# remote.net
KiCad netlist of a schematic drawn in EAGLE
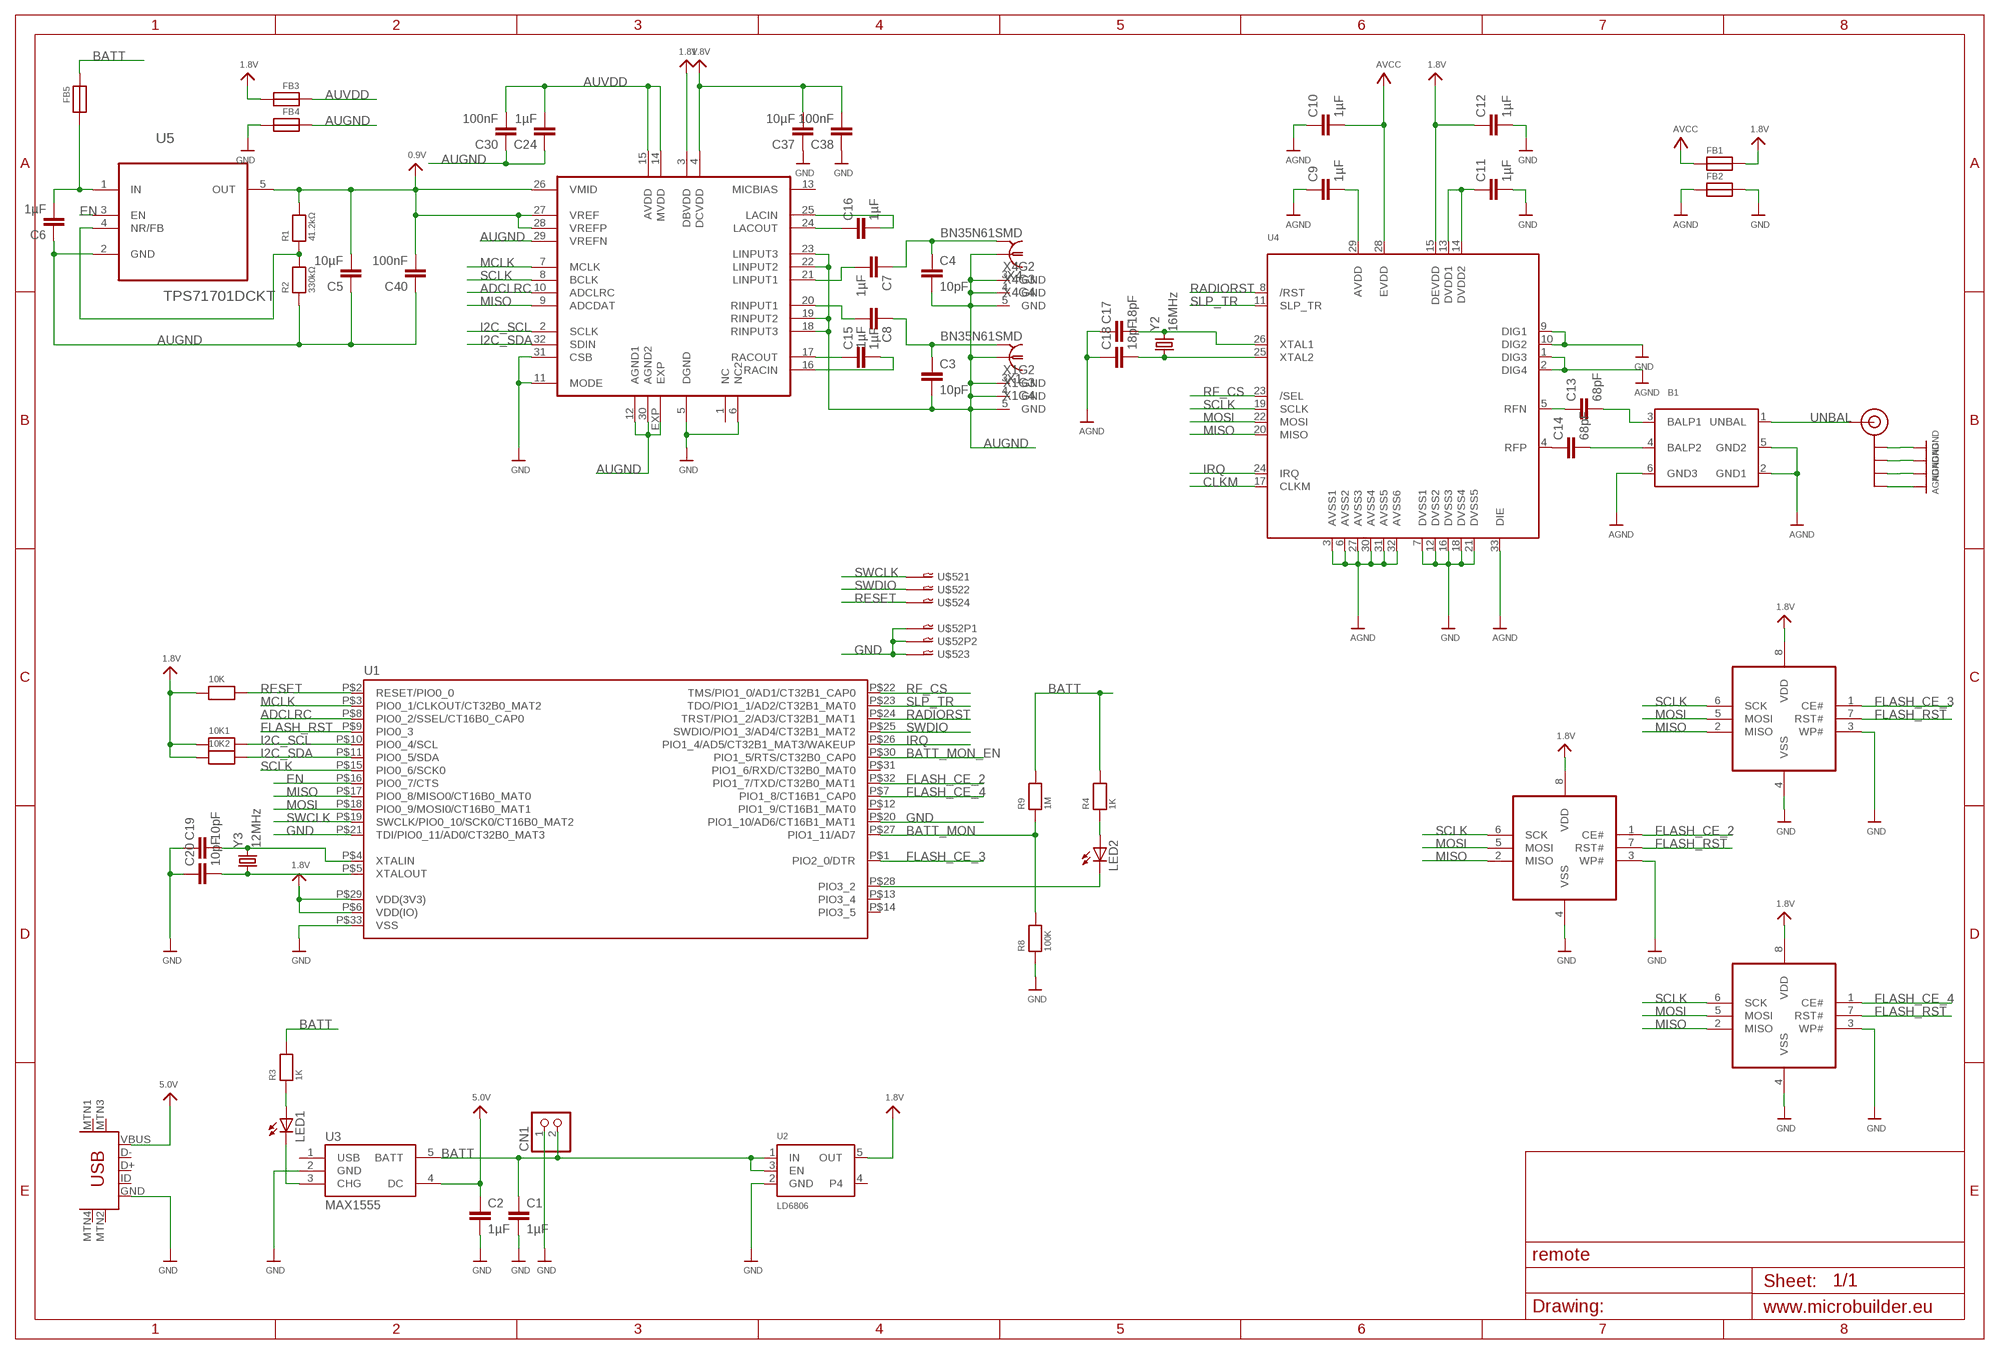
[diagram p0: schematic, sheet 1]

(export (version "E")
  (design (tool "Eeschema 10.0.6"))
  (components
    (comp (ref "10K")
      (value "RESISTOR0603MINI")
      (footprint "eagle-import:0603-MINI")
      (libsource (lib "eagle-import") (part "RESISTOR0603MINI"))
    )
    (comp (ref "10K1")
      (value "RESISTOR0603MINI")
      (footprint "eagle-import:0603-MINI")
      (libsource (lib "eagle-import") (part "RESISTOR0603MINI"))
    )
    (comp (ref "10K2")
      (value "RESISTOR0603MINI")
      (footprint "eagle-import:0603-MINI")
      (libsource (lib "eagle-import") (part "RESISTOR0603MINI"))
    )
    (comp (ref "B1")
      (value "BALUN+LP")
      (footprint "eagle-import:BALUN0805")
      (libsource (lib "eagle-import") (part "BALUN+LP"))
    )
    (comp (ref "C1")
      (value "1µF")
      (footprint "eagle-import:C0603K")
      (libsource (lib "eagle-import") (part "C-EUC0603K"))
    )
    (comp (ref "C2")
      (value "1µF")
      (footprint "eagle-import:C0603K")
      (libsource (lib "eagle-import") (part "C-EUC0603K"))
    )
    (comp (ref "C3")
      (value "10pF")
      (footprint "eagle-import:C0603K")
      (libsource (lib "eagle-import") (part "C-EUC0603K"))
    )
    (comp (ref "C4")
      (value "10pF")
      (footprint "eagle-import:C0603K")
      (libsource (lib "eagle-import") (part "C-EUC0603K"))
    )
    (comp (ref "C5")
      (value "10µF")
      (footprint "eagle-import:C0603K")
      (libsource (lib "eagle-import") (part "C-EUC0603K"))
    )
    (comp (ref "C6")
      (value "1µF")
      (footprint "eagle-import:C0603K")
      (libsource (lib "eagle-import") (part "C-EUC0603K"))
    )
    (comp (ref "C7")
      (value "1µF")
      (footprint "eagle-import:C0603K")
      (libsource (lib "eagle-import") (part "C-EUC0603K"))
    )
    (comp (ref "C8")
      (value "1µF")
      (footprint "eagle-import:C0603K")
      (libsource (lib "eagle-import") (part "C-EUC0603K"))
    )
    (comp (ref "C9")
      (value "1µF")
      (footprint "eagle-import:C0603K")
      (libsource (lib "eagle-import") (part "C-EUC0603K"))
    )
    (comp (ref "C10")
      (value "1µF")
      (footprint "eagle-import:C0603K")
      (libsource (lib "eagle-import") (part "C-EUC0603K"))
    )
    (comp (ref "C11")
      (value "1µF")
      (footprint "eagle-import:C0603K")
      (libsource (lib "eagle-import") (part "C-EUC0603K"))
    )
    (comp (ref "C12")
      (value "1µF")
      (footprint "eagle-import:C0603K")
      (libsource (lib "eagle-import") (part "C-EUC0603K"))
    )
    (comp (ref "C13")
      (value "68pF")
      (footprint "eagle-import:C0603K")
      (libsource (lib "eagle-import") (part "C-EUC0603K"))
    )
    (comp (ref "C14")
      (value "68pF")
      (footprint "eagle-import:C0603K")
      (libsource (lib "eagle-import") (part "C-EUC0603K"))
    )
    (comp (ref "C15")
      (value "1µF")
      (footprint "eagle-import:C0603K")
      (libsource (lib "eagle-import") (part "C-EUC0603K"))
    )
    (comp (ref "C16")
      (value "1µF")
      (footprint "eagle-import:C0603K")
      (libsource (lib "eagle-import") (part "C-EUC0603K"))
    )
    (comp (ref "C17")
      (value "18pF")
      (footprint "eagle-import:C0603K")
      (libsource (lib "eagle-import") (part "C-EUC0603K"))
    )
    (comp (ref "C18")
      (value "18pF")
      (footprint "eagle-import:C0603K")
      (libsource (lib "eagle-import") (part "C-EUC0603K"))
    )
    (comp (ref "C19")
      (value "10pF")
      (footprint "eagle-import:C0603K")
      (libsource (lib "eagle-import") (part "C-EUC0603K"))
    )
    (comp (ref "C20")
      (value "10pF")
      (footprint "eagle-import:C0603K")
      (libsource (lib "eagle-import") (part "C-EUC0603K"))
    )
    (comp (ref "C24")
      (value "1µF")
      (footprint "eagle-import:C0603K")
      (libsource (lib "eagle-import") (part "C-EUC0603K"))
    )
    (comp (ref "C30")
      (value "100nF")
      (footprint "eagle-import:C0603K")
      (libsource (lib "eagle-import") (part "C-EUC0603K"))
    )
    (comp (ref "C37")
      (value "10µF")
      (footprint "eagle-import:C0603K")
      (libsource (lib "eagle-import") (part "C-EUC0603K"))
    )
    (comp (ref "C38")
      (value "100nF")
      (footprint "eagle-import:C0603K")
      (libsource (lib "eagle-import") (part "C-EUC0603K"))
    )
    (comp (ref "C40")
      (value "100nF")
      (footprint "eagle-import:C0603K")
      (libsource (lib "eagle-import") (part "C-EUC0603K"))
    )
    (comp (ref "CN1")
      (value "JST_2PIN")
      (footprint "eagle-import:JSTPH2")
      (libsource (lib "eagle-import") (part "JST_2PIN"))
    )
    (comp (ref "FB1")
      (value "FERRITE")
      (footprint "eagle-import:0603")
      (libsource (lib "eagle-import") (part "FERRITE"))
    )
    (comp (ref "FB2")
      (value "FERRITE")
      (footprint "eagle-import:0603")
      (libsource (lib "eagle-import") (part "FERRITE"))
    )
    (comp (ref "FB3")
      (value "FERRITE")
      (footprint "eagle-import:0603")
      (libsource (lib "eagle-import") (part "FERRITE"))
    )
    (comp (ref "FB4")
      (value "FERRITE")
      (footprint "eagle-import:0603")
      (libsource (lib "eagle-import") (part "FERRITE"))
    )
    (comp (ref "FB5")
      (value "FERRITE")
      (footprint "eagle-import:0603")
      (libsource (lib "eagle-import") (part "FERRITE"))
    )
    (comp (ref "J$1")
      (value "SMA_EDGE")
      (footprint "eagle-import:SMA-EDGE")
      (libsource (lib "eagle-import") (part "SMA_EDGE"))
    )
    (comp (ref "LED1")
      (value "LEDCHIPLED_0603")
      (footprint "eagle-import:CHIPLED_0603")
      (libsource (lib "eagle-import") (part "LEDCHIPLED_0603"))
    )
    (comp (ref "LED2")
      (value "LEDCHIPLED_0603")
      (footprint "eagle-import:CHIPLED_0603")
      (libsource (lib "eagle-import") (part "LEDCHIPLED_0603"))
    )
    (comp (ref "R1")
      (value "41.2kΩ")
      (footprint "eagle-import:0603-MINI")
      (libsource (lib "eagle-import") (part "RESISTOR0603MINI"))
    )
    (comp (ref "R2")
      (value "330kΩ")
      (footprint "eagle-import:0603-MINI")
      (libsource (lib "eagle-import") (part "RESISTOR0603MINI"))
    )
    (comp (ref "R3")
      (value "1K")
      (footprint "eagle-import:0603-MINI")
      (libsource (lib "eagle-import") (part "RESISTOR0603MINI"))
    )
    (comp (ref "R4")
      (value "1K")
      (footprint "eagle-import:0603-MINI")
      (libsource (lib "eagle-import") (part "RESISTOR0603MINI"))
    )
    (comp (ref "R8")
      (value "100K")
      (footprint "eagle-import:0603-MINI")
      (libsource (lib "eagle-import") (part "RESISTOR0603MINI"))
    )
    (comp (ref "R9")
      (value "1M")
      (footprint "eagle-import:0603-MINI")
      (libsource (lib "eagle-import") (part "RESISTOR0603MINI"))
    )
    (comp (ref "U$1")
      (value "SST25WF")
      (footprint "eagle-import:ZA")
      (libsource (lib "eagle-import") (part "SST25WF"))
    )
    (comp (ref "U$14")
      (value "WM8737")
      (footprint "eagle-import:DM030FL")
      (libsource (lib "eagle-import") (part "WM8737"))
    )
    (comp (ref "U$16")
      (value "USB-MINIB-5PIN")
      (footprint "eagle-import:USB-MINIB")
      (libsource (lib "eagle-import") (part "USB-MINIB-5PIN"))
    )
    (comp (ref "U$22")
      (value "SST25WF")
      (footprint "eagle-import:ZA")
      (libsource (lib "eagle-import") (part "SST25WF"))
    )
    (comp (ref "U$26")
      (value "SST25WF")
      (footprint "eagle-import:ZA")
      (libsource (lib "eagle-import") (part "SST25WF"))
    )
    (comp (ref "U$52")
      (value "SM04B-SURS-TF")
      (footprint "eagle-import:SM04B-SURS-TF")
      (libsource (lib "eagle-import") (part "SM04B-SURS-TF"))
    )
    (comp (ref "U1")
      (value "LPC1113/4_QFN")
      (footprint "eagle-import:HVQFN33-7X7")
      (fields (field (name "MANF") "NXP"))
      (libsource (lib "eagle-import") (part "LPC1113/4_QFN"))
    )
    (comp (ref "U2")
      (value "LD6806")
      (footprint "eagle-import:SOT23-5")
      (libsource (lib "eagle-import") (part "VREG_SOT23-5"))
    )
    (comp (ref "U3")
      (value "MAX1555")
      (footprint "eagle-import:SOT23-5")
      (libsource (lib "eagle-import") (part "MAX1555"))
    )
    (comp (ref "U4")
      (value "AT86RF212")
      (footprint "eagle-import:32QN2")
      (libsource (lib "eagle-import") (part "AT86RF212"))
    )
    (comp (ref "U5")
      (value "TPS71701DCKT")
      (footprint "eagle-import:SOT65P210X110-5N")
      (libsource (lib "eagle-import") (part "TPS71701DCKT"))
    )
    (comp (ref "X1")
      (value "BN35N61SMD")
      (footprint "eagle-import:B35N61_SMD")
      (libsource (lib "eagle-import") (part "BN35N61SMD"))
    )
    (comp (ref "X4")
      (value "BN35N61SMD")
      (footprint "eagle-import:B35N61_SMD")
      (libsource (lib "eagle-import") (part "BN35N61SMD"))
    )
    (comp (ref "Y2")
      (value "16MHz")
      (footprint "eagle-import:CRYSTAL-SMD-5X3")
      (libsource (lib "eagle-import") (part "CRYSTAL5X3"))
    )
    (comp (ref "Y3")
      (value "12MHz")
      (footprint "eagle-import:CRYSTAL-SMD-5X3")
      (libsource (lib "eagle-import") (part "CRYSTAL5X3"))
    )
  )
  (nets
    (net (code "1") (name "/ADCLRC") (class "Default")
      (node (ref "U$14") (pin "10") (pinfunction "ADCLRC_10") (pintype "bidirectional"))
      (node (ref "U1") (pin "P$8") (pinfunction "PIO0_2/SSEL/CT16B0_CAP0_P$8") (pintype "bidirectional"))
    )
    (net (code "2") (name "/AUGND") (class "Default")
      (node (ref "C24") (pin "1") (pinfunction "1_1") (pintype "passive"))
      (node (ref "C3") (pin "2") (pinfunction "2_2") (pintype "passive"))
      (node (ref "C30") (pin "1") (pinfunction "1_1") (pintype "passive"))
      (node (ref "C4") (pin "2") (pinfunction "2_2") (pintype "passive"))
      (node (ref "C40") (pin "1") (pinfunction "1_1") (pintype "passive"))
      (node (ref "C5") (pin "1") (pinfunction "1_1") (pintype "passive"))
      (node (ref "C6") (pin "1") (pinfunction "1_1") (pintype "passive"))
      (node (ref "FB4") (pin "1") (pinfunction "P$1_1") (pintype "bidirectional"))
      (node (ref "R2") (pin "1") (pinfunction "1_1") (pintype "passive"))
      (node (ref "U$14") (pin "12") (pinfunction "AGND1_12") (pintype "bidirectional"))
      (node (ref "U$14") (pin "18") (pinfunction "RINPUT3_18") (pintype "bidirectional"))
      (node (ref "U$14") (pin "19") (pinfunction "RINPUT2_19") (pintype "bidirectional"))
      (node (ref "U$14") (pin "22") (pinfunction "LINPUT2_22") (pintype "bidirectional"))
      (node (ref "U$14") (pin "23") (pinfunction "LINPUT3_23") (pintype "bidirectional"))
      (node (ref "U$14") (pin "29") (pinfunction "VREFN_29") (pintype "bidirectional"))
      (node (ref "U$14") (pin "30") (pinfunction "AGND2_30") (pintype "bidirectional"))
      (node (ref "U$14") (pin "EXP") (pinfunction "EXP_EXP") (pintype "bidirectional"))
      (node (ref "U5") (pin "2") (pinfunction "GND_2") (pintype "passive"))
      (node (ref "X1") (pin "2") (pinfunction "1_2") (pintype "passive"))
      (node (ref "X1") (pin "3") (pinfunction "GND_3") (pintype "power_in"))
      (node (ref "X1") (pin "4") (pinfunction "GND_4") (pintype "power_in"))
      (node (ref "X1") (pin "5") (pinfunction "GND_5") (pintype "power_in"))
      (node (ref "X4") (pin "2") (pinfunction "1_2") (pintype "passive"))
      (node (ref "X4") (pin "3") (pinfunction "GND_3") (pintype "power_in"))
      (node (ref "X4") (pin "4") (pinfunction "GND_4") (pintype "power_in"))
      (node (ref "X4") (pin "5") (pinfunction "GND_5") (pintype "power_in"))
    )
    (net (code "3") (name "/AUVDD") (class "Default")
      (node (ref "C24") (pin "2") (pinfunction "2_2") (pintype "passive"))
      (node (ref "C30") (pin "2") (pinfunction "2_2") (pintype "passive"))
      (node (ref "FB3") (pin "1") (pinfunction "P$1_1") (pintype "bidirectional"))
      (node (ref "U$14") (pin "14") (pinfunction "MVDD_14") (pintype "bidirectional"))
      (node (ref "U$14") (pin "15") (pinfunction "AVDD_15") (pintype "bidirectional"))
    )
    (net (code "4") (name "/BATT") (class "Default")
      (node (ref "C1") (pin "1") (pinfunction "1_1") (pintype "passive"))
      (node (ref "CN1") (pin "2") (pinfunction "2_2") (pintype "passive"))
      (node (ref "FB5") (pin "1") (pinfunction "P$1_1") (pintype "bidirectional"))
      (node (ref "R3") (pin "2") (pinfunction "2_2") (pintype "passive"))
      (node (ref "R4") (pin "2") (pinfunction "2_2") (pintype "passive"))
      (node (ref "R9") (pin "2") (pinfunction "2_2") (pintype "passive"))
      (node (ref "U2") (pin "1") (pinfunction "IN_1") (pintype "bidirectional"))
      (node (ref "U2") (pin "3") (pinfunction "EN_3") (pintype "bidirectional"))
      (node (ref "U3") (pin "5") (pinfunction "BATT_5") (pintype "bidirectional"))
    )
    (net (code "5") (name "/BATT_MON") (class "Default")
      (node (ref "R8") (pin "2") (pinfunction "2_2") (pintype "passive"))
      (node (ref "R9") (pin "1") (pinfunction "1_1") (pintype "passive"))
      (node (ref "U1") (pin "P$27") (pinfunction "PIO1_11/AD7_P$27") (pintype "bidirectional"))
    )
    (net (code "6") (name "/BATT_MON_EN") (class "Default")
      (node (ref "U1") (pin "P$30") (pinfunction "PIO1_5/RTS/CT32B0_CAP0_P$30") (pintype "bidirectional"))
    )
    (net (code "7") (name "/CLKM") (class "Default")
      (node (ref "U4") (pin "17") (pinfunction "CLKM_17") (pintype "bidirectional"))
    )
    (net (code "8") (name "/EN") (class "Default")
      (node (ref "U1") (pin "P$16") (pinfunction "PIO0_7/CTS_P$16") (pintype "bidirectional"))
      (node (ref "U5") (pin "3") (pinfunction "EN_3") (pintype "input"))
    )
    (net (code "9") (name "/FLASH_CE_2") (class "Default")
      (node (ref "U$26") (pin "1") (pinfunction "CE#_1") (pintype "bidirectional"))
      (node (ref "U1") (pin "P$32") (pinfunction "PIO1_7/TXD/CT32B0_MAT1_P$32") (pintype "bidirectional"))
    )
    (net (code "10") (name "/FLASH_CE_3") (class "Default")
      (node (ref "U$22") (pin "1") (pinfunction "CE#_1") (pintype "bidirectional"))
      (node (ref "U1") (pin "P$1") (pinfunction "PIO2_0/DTR_P$1") (pintype "bidirectional"))
    )
    (net (code "11") (name "/FLASH_CE_4") (class "Default")
      (node (ref "U$1") (pin "1") (pinfunction "CE#_1") (pintype "bidirectional"))
      (node (ref "U1") (pin "P$7") (pinfunction "PIO1_8/CT16B1_CAP0_P$7") (pintype "bidirectional"))
    )
    (net (code "12") (name "/FLASH_RST") (class "Default")
      (node (ref "U$1") (pin "7") (pinfunction "RST#_7") (pintype "bidirectional"))
      (node (ref "U$22") (pin "7") (pinfunction "RST#_7") (pintype "bidirectional"))
      (node (ref "U$26") (pin "7") (pinfunction "RST#_7") (pintype "bidirectional"))
      (node (ref "U1") (pin "P$9") (pinfunction "PIO0_3_P$9") (pintype "bidirectional"))
    )
    (net (code "13") (name "/I2C_SCL") (class "Default")
      (node (ref "10K1") (pin "2") (pinfunction "2_2") (pintype "passive"))
      (node (ref "U$14") (pin "2") (pinfunction "SCLK_2") (pintype "bidirectional"))
      (node (ref "U1") (pin "P$10") (pinfunction "PIO0_4/SCL_P$10") (pintype "bidirectional"))
    )
    (net (code "14") (name "/I2C_SDA") (class "Default")
      (node (ref "10K2") (pin "2") (pinfunction "2_2") (pintype "passive"))
      (node (ref "U$14") (pin "32") (pinfunction "SDIN_32") (pintype "bidirectional"))
      (node (ref "U1") (pin "P$11") (pinfunction "PIO0_5/SDA_P$11") (pintype "bidirectional"))
    )
    (net (code "15") (name "/IRQ") (class "Default")
      (node (ref "U1") (pin "P$26") (pinfunction "PIO1_4/AD5/CT32B1_MAT3/WAKEUP_P$26") (pintype "bidirectional"))
      (node (ref "U4") (pin "24") (pinfunction "IRQ_24") (pintype "bidirectional"))
    )
    (net (code "16") (name "/MCLK") (class "Default")
      (node (ref "U$14") (pin "7") (pinfunction "MCLK_7") (pintype "bidirectional"))
      (node (ref "U1") (pin "P$3") (pinfunction "PIO0_1/CLKOUT/CT32B0_MAT2_P$3") (pintype "bidirectional"))
    )
    (net (code "17") (name "/MISO") (class "Default")
      (node (ref "U$1") (pin "2") (pinfunction "MISO_2") (pintype "bidirectional"))
      (node (ref "U$14") (pin "9") (pinfunction "ADCDAT_9") (pintype "bidirectional"))
      (node (ref "U$22") (pin "2") (pinfunction "MISO_2") (pintype "bidirectional"))
      (node (ref "U$26") (pin "2") (pinfunction "MISO_2") (pintype "bidirectional"))
      (node (ref "U1") (pin "P$17") (pinfunction "PIO0_8/MISO0/CT16B0_MAT0_P$17") (pintype "bidirectional"))
      (node (ref "U4") (pin "20") (pinfunction "MISO_20") (pintype "bidirectional"))
    )
    (net (code "18") (name "/MOSI") (class "Default")
      (node (ref "U$1") (pin "5") (pinfunction "MOSI_5") (pintype "bidirectional"))
      (node (ref "U$22") (pin "5") (pinfunction "MOSI_5") (pintype "bidirectional"))
      (node (ref "U$26") (pin "5") (pinfunction "MOSI_5") (pintype "bidirectional"))
      (node (ref "U1") (pin "P$18") (pinfunction "PIO0_9/MOSI0/CT16B0_MAT1_P$18") (pintype "bidirectional"))
      (node (ref "U4") (pin "22") (pinfunction "MOSI_22") (pintype "bidirectional"))
    )
    (net (code "19") (name "/RADIORST") (class "Default")
      (node (ref "U1") (pin "P$24") (pinfunction "TRST/PIO1_2/AD3/CT32B1_MAT1_P$24") (pintype "bidirectional"))
      (node (ref "U4") (pin "8") (pinfunction "/RST_8") (pintype "bidirectional"))
    )
    (net (code "20") (name "/RESET") (class "Default")
      (node (ref "10K") (pin "2") (pinfunction "2_2") (pintype "passive"))
      (node (ref "U$52") (pin "4") (pinfunction "1_4") (pintype "passive"))
      (node (ref "U1") (pin "P$2") (pinfunction "RESET/PIO0_0_P$2") (pintype "bidirectional"))
    )
    (net (code "21") (name "/RF_CS") (class "Default")
      (node (ref "U1") (pin "P$22") (pinfunction "TMS/PIO1_0/AD1/CT32B1_CAP0_P$22") (pintype "bidirectional"))
      (node (ref "U4") (pin "23") (pinfunction "/SEL_23") (pintype "bidirectional"))
    )
    (net (code "22") (name "/SCLK") (class "Default")
      (node (ref "U$1") (pin "6") (pinfunction "SCK_6") (pintype "bidirectional"))
      (node (ref "U$14") (pin "8") (pinfunction "BCLK_8") (pintype "bidirectional"))
      (node (ref "U$22") (pin "6") (pinfunction "SCK_6") (pintype "bidirectional"))
      (node (ref "U$26") (pin "6") (pinfunction "SCK_6") (pintype "bidirectional"))
      (node (ref "U1") (pin "P$15") (pinfunction "PIO0_6/SCK0_P$15") (pintype "bidirectional"))
      (node (ref "U4") (pin "19") (pinfunction "SCLK_19") (pintype "bidirectional"))
    )
    (net (code "23") (name "/SLP_TR") (class "Default")
      (node (ref "U1") (pin "P$23") (pinfunction "TDO/PIO1_1/AD2/CT32B1_MAT0_P$23") (pintype "bidirectional"))
      (node (ref "U4") (pin "11") (pinfunction "SLP_TR_11") (pintype "bidirectional"))
    )
    (net (code "24") (name "/SWCLK") (class "Default")
      (node (ref "U$52") (pin "1") (pinfunction "1_1") (pintype "passive"))
      (node (ref "U1") (pin "P$19") (pinfunction "SWCLK/PIO0_10/SCK0/CT16B0_MAT2_P$19") (pintype "bidirectional"))
    )
    (net (code "25") (name "/SWDIO") (class "Default")
      (node (ref "U$52") (pin "2") (pinfunction "1_2") (pintype "passive"))
      (node (ref "U1") (pin "P$25") (pinfunction "SWDIO/PIO1_3/AD4/CT32B1_MAT2_P$25") (pintype "bidirectional"))
    )
    (net (code "26") (name "/UNBAL") (class "Default")
      (node (ref "B1") (pin "1") (pinfunction "UNBAL_1") (pintype "bidirectional"))
      (node (ref "J$1") (pin "SIG") (pinfunction "SIGNAL_SIG") (pintype "bidirectional"))
    )
    (net (code "27") (name "0.9V") (class "Default")
      (node (ref "C40") (pin "2") (pinfunction "2_2") (pintype "passive"))
      (node (ref "C5") (pin "2") (pinfunction "2_2") (pintype "passive"))
      (node (ref "R1") (pin "2") (pinfunction "2_2") (pintype "passive"))
      (node (ref "U$14") (pin "26") (pinfunction "VMID_26") (pintype "bidirectional"))
      (node (ref "U$14") (pin "27") (pinfunction "VREF_27") (pintype "bidirectional"))
      (node (ref "U$14") (pin "28") (pinfunction "VREFP_28") (pintype "bidirectional"))
      (node (ref "U5") (pin "5") (pinfunction "OUT_5") (pintype "output"))
    )
    (net (code "28") (name "1.8V") (class "Default")
      (node (ref "10K") (pin "1") (pinfunction "1_1") (pintype "passive"))
      (node (ref "10K1") (pin "1") (pinfunction "1_1") (pintype "passive"))
      (node (ref "10K2") (pin "1") (pinfunction "1_1") (pintype "passive"))
      (node (ref "C12") (pin "1") (pinfunction "1_1") (pintype "passive"))
      (node (ref "C37") (pin "2") (pinfunction "2_2") (pintype "passive"))
      (node (ref "C38") (pin "2") (pinfunction "2_2") (pintype "passive"))
      (node (ref "FB1") (pin "2") (pinfunction "P$2_2") (pintype "bidirectional"))
      (node (ref "FB3") (pin "2") (pinfunction "P$2_2") (pintype "bidirectional"))
      (node (ref "U$1") (pin "8") (pinfunction "VDD_8") (pintype "bidirectional"))
      (node (ref "U$14") (pin "3") (pinfunction "DBVDD_3") (pintype "bidirectional"))
      (node (ref "U$14") (pin "4") (pinfunction "DCVDD_4") (pintype "bidirectional"))
      (node (ref "U$22") (pin "8") (pinfunction "VDD_8") (pintype "bidirectional"))
      (node (ref "U$26") (pin "8") (pinfunction "VDD_8") (pintype "bidirectional"))
      (node (ref "U1") (pin "P$29") (pinfunction "VDD(3V3)_P$29") (pintype "power_in"))
      (node (ref "U1") (pin "P$6") (pinfunction "VDD(IO)_P$6") (pintype "power_in"))
      (node (ref "U2") (pin "5") (pinfunction "OUT_5") (pintype "bidirectional"))
      (node (ref "U4") (pin "15") (pinfunction "DEVDD_15") (pintype "bidirectional"))
    )
    (net (code "29") (name "5.0V") (class "Default")
      (node (ref "C2") (pin "1") (pinfunction "1_1") (pintype "passive"))
      (node (ref "U$16") (pin "VBUS") (pinfunction "VBUS_VBUS") (pintype "bidirectional"))
      (node (ref "U3") (pin "4") (pinfunction "DC_4") (pintype "bidirectional"))
    )
    (net (code "30") (name "AGND") (class "Default")
      (node (ref "B1") (pin "2") (pinfunction "GND1_2") (pintype "bidirectional"))
      (node (ref "B1") (pin "5") (pinfunction "GND2_5") (pintype "bidirectional"))
      (node (ref "B1") (pin "6") (pinfunction "GND3_6") (pintype "bidirectional"))
      (node (ref "C10") (pin "1") (pinfunction "1_1") (pintype "passive"))
      (node (ref "C17") (pin "1") (pinfunction "1_1") (pintype "passive"))
      (node (ref "C18") (pin "1") (pinfunction "1_1") (pintype "passive"))
      (node (ref "C9") (pin "1") (pinfunction "1_1") (pintype "passive"))
      (node (ref "FB2") (pin "1") (pinfunction "P$1_1") (pintype "bidirectional"))
      (node (ref "J$1") (pin "GND@0") (pinfunction "GND_GND@0") (pintype "bidirectional"))
      (node (ref "J$1") (pin "GND@1") (pinfunction "GND_GND@1") (pintype "bidirectional"))
      (node (ref "J$1") (pin "GND@2") (pinfunction "GND_GND@2") (pintype "bidirectional"))
      (node (ref "J$1") (pin "GND@3") (pinfunction "GND_GND@3") (pintype "bidirectional"))
      (node (ref "U4") (pin "1") (pinfunction "DIG3_1") (pintype "bidirectional"))
      (node (ref "U4") (pin "2") (pinfunction "DIG4_2") (pintype "bidirectional"))
      (node (ref "U4") (pin "27") (pinfunction "AVSS3_27") (pintype "bidirectional"))
      (node (ref "U4") (pin "3") (pinfunction "AVSS1_3") (pintype "bidirectional"))
      (node (ref "U4") (pin "30") (pinfunction "AVSS4_30") (pintype "bidirectional"))
      (node (ref "U4") (pin "31") (pinfunction "AVSS5_31") (pintype "bidirectional"))
      (node (ref "U4") (pin "32") (pinfunction "AVSS6_32") (pintype "bidirectional"))
      (node (ref "U4") (pin "33") (pinfunction "DIE_33") (pintype "bidirectional"))
      (node (ref "U4") (pin "6") (pinfunction "AVSS2_6") (pintype "bidirectional"))
    )
    (net (code "31") (name "AVCC") (class "Default")
      (node (ref "C10") (pin "2") (pinfunction "2_2") (pintype "passive"))
      (node (ref "FB1") (pin "1") (pinfunction "P$1_1") (pintype "bidirectional"))
      (node (ref "U4") (pin "28") (pinfunction "EVDD_28") (pintype "bidirectional"))
    )
    (net (code "32") (name "GND") (class "Default")
      (node (ref "C1") (pin "2") (pinfunction "2_2") (pintype "passive"))
      (node (ref "C11") (pin "2") (pinfunction "2_2") (pintype "passive"))
      (node (ref "C12") (pin "2") (pinfunction "2_2") (pintype "passive"))
      (node (ref "C19") (pin "1") (pinfunction "1_1") (pintype "passive"))
      (node (ref "C2") (pin "2") (pinfunction "2_2") (pintype "passive"))
      (node (ref "C20") (pin "1") (pinfunction "1_1") (pintype "passive"))
      (node (ref "C37") (pin "1") (pinfunction "1_1") (pintype "passive"))
      (node (ref "C38") (pin "1") (pinfunction "1_1") (pintype "passive"))
      (node (ref "CN1") (pin "1") (pinfunction "1_1") (pintype "passive"))
      (node (ref "FB2") (pin "2") (pinfunction "P$2_2") (pintype "bidirectional"))
      (node (ref "FB4") (pin "2") (pinfunction "P$2_2") (pintype "bidirectional"))
      (node (ref "R8") (pin "1") (pinfunction "1_1") (pintype "passive"))
      (node (ref "U$1") (pin "3") (pinfunction "WP#_3") (pintype "bidirectional"))
      (node (ref "U$1") (pin "4") (pinfunction "VSS_4") (pintype "bidirectional"))
      (node (ref "U$14") (pin "11") (pinfunction "MODE_11") (pintype "bidirectional"))
      (node (ref "U$14") (pin "31") (pinfunction "CSB_31") (pintype "bidirectional"))
      (node (ref "U$14") (pin "5") (pinfunction "DGND_5") (pintype "bidirectional"))
      (node (ref "U$14") (pin "6") (pinfunction "NC2_6") (pintype "bidirectional"))
      (node (ref "U$16") (pin "GND") (pinfunction "GND_GND") (pintype "bidirectional"))
      (node (ref "U$22") (pin "3") (pinfunction "WP#_3") (pintype "bidirectional"))
      (node (ref "U$22") (pin "4") (pinfunction "VSS_4") (pintype "bidirectional"))
      (node (ref "U$26") (pin "3") (pinfunction "WP#_3") (pintype "bidirectional"))
      (node (ref "U$26") (pin "4") (pinfunction "VSS_4") (pintype "bidirectional"))
      (node (ref "U$52") (pin "3") (pinfunction "1_3") (pintype "passive"))
      (node (ref "U$52") (pin "GND1") (pinfunction "1_GND1") (pintype "passive"))
      (node (ref "U$52") (pin "GND2") (pinfunction "1_GND2") (pintype "passive"))
      (node (ref "U1") (pin "P$20") (pinfunction "PIO1_10/AD6/CT16B1_MAT1_P$20") (pintype "bidirectional"))
      (node (ref "U1") (pin "P$21") (pinfunction "TDI/PIO0_11/AD0/CT32B0_MAT3_P$21") (pintype "bidirectional"))
      (node (ref "U1") (pin "P$33") (pinfunction "VSS_P$33") (pintype "power_in"))
      (node (ref "U2") (pin "2") (pinfunction "GND_2") (pintype "bidirectional"))
      (node (ref "U3") (pin "2") (pinfunction "GND_2") (pintype "bidirectional"))
      (node (ref "U4") (pin "10") (pinfunction "DIG2_10") (pintype "bidirectional"))
      (node (ref "U4") (pin "12") (pinfunction "DVSS2_12") (pintype "bidirectional"))
      (node (ref "U4") (pin "16") (pinfunction "DVSS3_16") (pintype "bidirectional"))
      (node (ref "U4") (pin "18") (pinfunction "DVSS4_18") (pintype "bidirectional"))
      (node (ref "U4") (pin "21") (pinfunction "DVSS5_21") (pintype "bidirectional"))
      (node (ref "U4") (pin "7") (pinfunction "DVSS1_7") (pintype "bidirectional"))
      (node (ref "U4") (pin "9") (pinfunction "DIG1_9") (pintype "bidirectional"))
    )
    (net (code "33") (name "Net-(B1-BALP1)") (class "Default")
      (node (ref "B1") (pin "3") (pinfunction "BALP1_3") (pintype "bidirectional"))
      (node (ref "C13") (pin "2") (pinfunction "2_2") (pintype "passive"))
    )
    (net (code "34") (name "Net-(B1-BALP2)") (class "Default")
      (node (ref "B1") (pin "4") (pinfunction "BALP2_4") (pintype "bidirectional"))
      (node (ref "C14") (pin "2") (pinfunction "2_2") (pintype "passive"))
    )
    (net (code "35") (name "Net-(FB5-P$2)") (class "Default")
      (node (ref "C6") (pin "2") (pinfunction "2_2") (pintype "passive"))
      (node (ref "FB5") (pin "2") (pinfunction "P$2_2") (pintype "bidirectional"))
      (node (ref "U5") (pin "1") (pinfunction "IN_1") (pintype "power_in"))
    )
    (net (code "36") (name "Net-(LED1-PadA)") (class "Default")
      (node (ref "LED1") (pin "A") (pinfunction "A_A") (pintype "passive"))
      (node (ref "R3") (pin "1") (pinfunction "1_1") (pintype "passive"))
    )
    (net (code "37") (name "Net-(LED2-PadA)") (class "Default")
      (node (ref "LED2") (pin "A") (pinfunction "A_A") (pintype "passive"))
      (node (ref "R4") (pin "1") (pinfunction "1_1") (pintype "passive"))
    )
    (net (code "38") (name "Net-(U$14-LACIN)") (class "Default")
      (node (ref "C16") (pin "2") (pinfunction "2_2") (pintype "passive"))
      (node (ref "U$14") (pin "25") (pinfunction "LACIN_25") (pintype "bidirectional"))
    )
    (net (code "39") (name "Net-(U$14-LACOUT)") (class "Default")
      (node (ref "C16") (pin "1") (pinfunction "1_1") (pintype "passive"))
      (node (ref "U$14") (pin "24") (pinfunction "LACOUT_24") (pintype "bidirectional"))
    )
    (net (code "40") (name "Net-(U$14-LINPUT1)") (class "Default")
      (node (ref "C7") (pin "2") (pinfunction "2_2") (pintype "passive"))
      (node (ref "U$14") (pin "21") (pinfunction "LINPUT1_21") (pintype "bidirectional"))
    )
    (net (code "41") (name "Net-(U$14-RACIN)") (class "Default")
      (node (ref "C15") (pin "2") (pinfunction "2_2") (pintype "passive"))
      (node (ref "U$14") (pin "16") (pinfunction "RACIN_16") (pintype "bidirectional"))
    )
    (net (code "42") (name "Net-(U$14-RACOUT)") (class "Default")
      (node (ref "C15") (pin "1") (pinfunction "1_1") (pintype "passive"))
      (node (ref "U$14") (pin "17") (pinfunction "RACOUT_17") (pintype "bidirectional"))
    )
    (net (code "43") (name "Net-(U$14-RINPUT1)") (class "Default")
      (node (ref "C8") (pin "2") (pinfunction "2_2") (pintype "passive"))
      (node (ref "U$14") (pin "20") (pinfunction "RINPUT1_20") (pintype "bidirectional"))
    )
    (net (code "44") (name "Net-(U1-PIO3_2)") (class "Default")
      (node (ref "LED2") (pin "C") (pinfunction "C_C") (pintype "passive"))
      (node (ref "U1") (pin "P$28") (pinfunction "PIO3_2_P$28") (pintype "bidirectional"))
    )
    (net (code "45") (name "Net-(U1-XTALIN)") (class "Default")
      (node (ref "C19") (pin "2") (pinfunction "2_2") (pintype "passive"))
      (node (ref "U1") (pin "P$4") (pinfunction "XTALIN_P$4") (pintype "input"))
      (node (ref "Y3") (pin "3") (pinfunction "2_3") (pintype "passive"))
    )
    (net (code "46") (name "Net-(U1-XTALOUT)") (class "Default")
      (node (ref "C20") (pin "2") (pinfunction "2_2") (pintype "passive"))
      (node (ref "U1") (pin "P$5") (pinfunction "XTALOUT_P$5") (pintype "output"))
      (node (ref "Y3") (pin "1") (pinfunction "1_1") (pintype "passive"))
    )
    (net (code "47") (name "Net-(U3-CHG)") (class "Default")
      (node (ref "LED1") (pin "C") (pinfunction "C_C") (pintype "passive"))
      (node (ref "U3") (pin "3") (pinfunction "CHG_3") (pintype "bidirectional"))
    )
    (net (code "48") (name "Net-(U4-AVDD)") (class "Default")
      (node (ref "C9") (pin "2") (pinfunction "2_2") (pintype "passive"))
      (node (ref "U4") (pin "29") (pinfunction "AVDD_29") (pintype "bidirectional"))
    )
    (net (code "49") (name "Net-(U4-DVDD1)") (class "Default")
      (node (ref "C11") (pin "1") (pinfunction "1_1") (pintype "passive"))
      (node (ref "U4") (pin "13") (pinfunction "DVDD1_13") (pintype "bidirectional"))
      (node (ref "U4") (pin "14") (pinfunction "DVDD2_14") (pintype "bidirectional"))
    )
    (net (code "50") (name "Net-(U4-RFN)") (class "Default")
      (node (ref "C13") (pin "1") (pinfunction "1_1") (pintype "passive"))
      (node (ref "U4") (pin "5") (pinfunction "RFN_5") (pintype "bidirectional"))
    )
    (net (code "51") (name "Net-(U4-RFP)") (class "Default")
      (node (ref "C14") (pin "1") (pinfunction "1_1") (pintype "passive"))
      (node (ref "U4") (pin "4") (pinfunction "RFP_4") (pintype "bidirectional"))
    )
    (net (code "52") (name "Net-(U4-XTAL1)") (class "Default")
      (node (ref "C17") (pin "2") (pinfunction "2_2") (pintype "passive"))
      (node (ref "U4") (pin "26") (pinfunction "XTAL1_26") (pintype "bidirectional"))
      (node (ref "Y2") (pin "3") (pinfunction "2_3") (pintype "passive"))
    )
    (net (code "53") (name "Net-(U4-XTAL2)") (class "Default")
      (node (ref "C18") (pin "2") (pinfunction "2_2") (pintype "passive"))
      (node (ref "U4") (pin "25") (pinfunction "XTAL2_25") (pintype "bidirectional"))
      (node (ref "Y2") (pin "1") (pinfunction "1_1") (pintype "passive"))
    )
    (net (code "54") (name "Net-(U5-NR{slash}FB)") (class "Default")
      (node (ref "R1") (pin "1") (pinfunction "1_1") (pintype "passive"))
      (node (ref "R2") (pin "2") (pinfunction "2_2") (pintype "passive"))
      (node (ref "U5") (pin "4") (pinfunction "NR/FB_4") (pintype "input"))
    )
    (net (code "55") (name "Net-(X1A-GND)") (class "Default")
      (node (ref "C3") (pin "1") (pinfunction "1_1") (pintype "passive"))
      (node (ref "C8") (pin "1") (pinfunction "1_1") (pintype "passive"))
      (node (ref "X1") (pin "1") (pinfunction "GND_1") (pintype "power_in"))
    )
    (net (code "56") (name "Net-(X4A-GND)") (class "Default")
      (node (ref "C4") (pin "1") (pinfunction "1_1") (pintype "passive"))
      (node (ref "C7") (pin "1") (pinfunction "1_1") (pintype "passive"))
      (node (ref "X4") (pin "1") (pinfunction "GND_1") (pintype "power_in"))
    )
    (net (code "57") (name "unconnected-(U$14-MICBIAS-Pad13)") (class "Default")
      (node (ref "U$14") (pin "13") (pinfunction "MICBIAS_13") (pintype "bidirectional"))
    )
    (net (code "58") (name "unconnected-(U$14-NC-Pad1)") (class "Default")
      (node (ref "U$14") (pin "1") (pinfunction "NC_1") (pintype "bidirectional"))
    )
    (net (code "59") (name "unconnected-(U$16-MTN1-PadMTN3)") (class "Default")
      (node (ref "U$16") (pin "MTN3") (pinfunction "MTN1_MTN3") (pintype "bidirectional"))
    )
    (net (code "60") (name "unconnected-(U$16-MTN2-PadMTN1)") (class "Default")
      (node (ref "U$16") (pin "MTN1") (pinfunction "MTN2_MTN1") (pintype "bidirectional"))
    )
    (net (code "61") (name "unconnected-(U$16-MTN3-PadMTN2)") (class "Default")
      (node (ref "U$16") (pin "MTN2") (pinfunction "MTN3_MTN2") (pintype "bidirectional"))
    )
    (net (code "62") (name "unconnected-(U$16-PadD+)") (class "Default")
      (node (ref "U$16") (pin "D+") (pinfunction "D+_D+") (pintype "bidirectional"))
    )
    (net (code "63") (name "unconnected-(U$16-PadD-)") (class "Default")
      (node (ref "U$16") (pin "D-") (pinfunction "D-_D-") (pintype "bidirectional"))
    )
    (net (code "64") (name "unconnected-(U$16-PadID)") (class "Default")
      (node (ref "U$16") (pin "ID") (pinfunction "ID_ID") (pintype "bidirectional"))
    )
    (net (code "65") (name "unconnected-(U$16-PadMTN4)") (class "Default")
      (node (ref "U$16") (pin "MTN4") (pinfunction "MTN4_MTN4") (pintype "bidirectional"))
    )
    (net (code "66") (name "unconnected-(U1-PIO1_6{slash}RXD{slash}CT32B0_MAT0-PadP$31)") (class "Default")
      (node (ref "U1") (pin "P$31") (pinfunction "PIO1_6/RXD/CT32B0_MAT0_P$31") (pintype "bidirectional"))
    )
    (net (code "67") (name "unconnected-(U1-PIO1_9{slash}CT16B1_MAT0-PadP$12)") (class "Default")
      (node (ref "U1") (pin "P$12") (pinfunction "PIO1_9/CT16B1_MAT0_P$12") (pintype "bidirectional"))
    )
    (net (code "68") (name "unconnected-(U1-PIO3_4-PadP$13)") (class "Default")
      (node (ref "U1") (pin "P$13") (pinfunction "PIO3_4_P$13") (pintype "bidirectional"))
    )
    (net (code "69") (name "unconnected-(U1-PIO3_5-PadP$14)") (class "Default")
      (node (ref "U1") (pin "P$14") (pinfunction "PIO3_5_P$14") (pintype "bidirectional"))
    )
    (net (code "70") (name "unconnected-(U2-P4-Pad4)") (class "Default")
      (node (ref "U2") (pin "4") (pinfunction "P4_4") (pintype "bidirectional"))
    )
    (net (code "71") (name "unconnected-(U3-USB-Pad1)") (class "Default")
      (node (ref "U3") (pin "1") (pinfunction "USB_1") (pintype "bidirectional"))
    )
  )
)
